# esquematico.net
KiCad netlist of a schematic drawn in Altium Designer
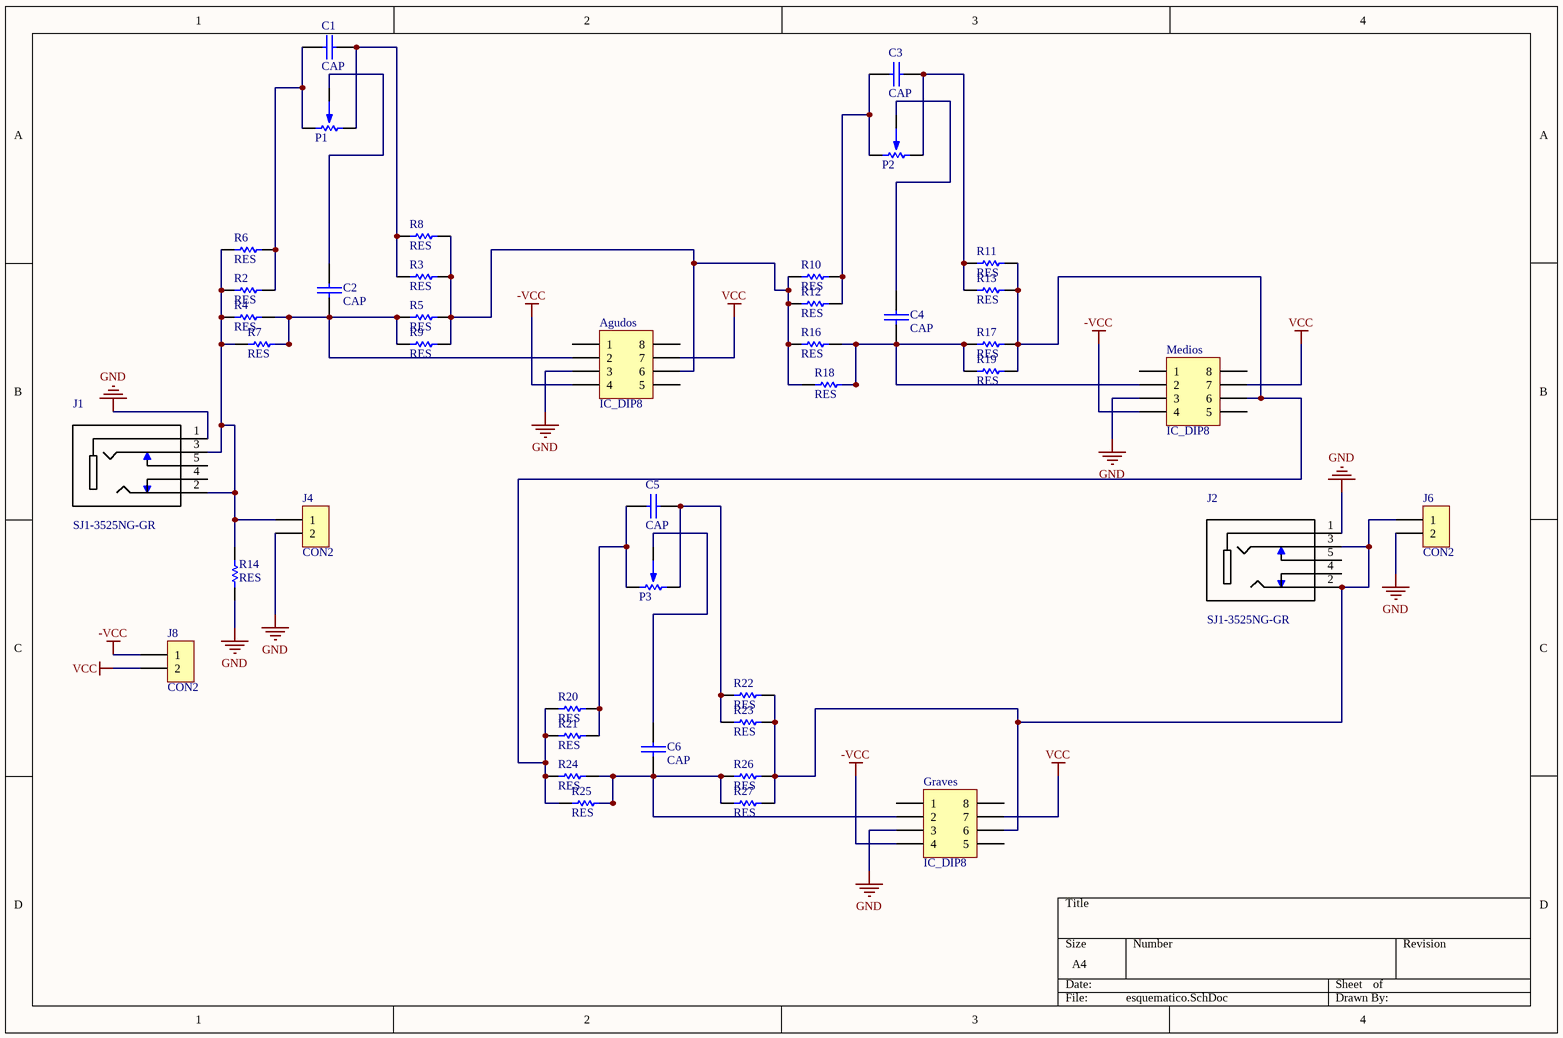
[diagram p0: esquematico.SchDoc]

(export (version "E")
  (design (tool "Eeschema 10.0.6"))
  (components
    (comp (ref "Agudos") (value "IC_DIP8") (footprint "DIP8") (libsource (lib "LIBEBAL") (part "IC_DIP8")))
    (comp (ref "C1") (value "CAP") (footprint "CAP200") (libsource (lib "LIBEBAL") (part "CAP")))
    (comp (ref "C2") (value "CAP") (footprint "CAP200") (libsource (lib "LIBEBAL") (part "CAP")))
    (comp (ref "C3") (value "CAP") (footprint "CAP200") (libsource (lib "LIBEBAL") (part "CAP")))
    (comp (ref "C4") (value "CAP") (footprint "CAP200") (libsource (lib "LIBEBAL") (part "CAP")))
    (comp (ref "C5") (value "CAP") (footprint "CAP200") (libsource (lib "LIBEBAL") (part "CAP")))
    (comp (ref "C6") (value "CAP") (footprint "CAP200") (libsource (lib "LIBEBAL") (part "CAP")))
    (comp (ref "Graves") (value "IC_DIP8") (footprint "DIP8") (libsource (lib "LIBEBAL") (part "IC_DIP8")))
    (comp (ref "J1")
      (value "SJ1-3525NG-GR")
      (footprint "CUI_SJ1-3525NG-GR")
      (libsource (lib "SJ1-3525NG-GR") (part "SJ1-3525NG-GR"))
    )
    (comp (ref "J2")
      (value "SJ1-3525NG-GR")
      (footprint "CUI_SJ1-3525NG-GR")
      (libsource (lib "SJ1-3525NG-GR") (part "SJ1-3525NG-GR"))
    )
    (comp (ref "J4") (value "CON2") (footprint "SIP2") (libsource (lib "LIBEBAL") (part "CON2")))
    (comp (ref "J6") (value "CON2") (footprint "SIP2") (libsource (lib "LIBEBAL") (part "CON2")))
    (comp (ref "J8") (value "CON2") (footprint "SIP2") (libsource (lib "LIBEBAL") (part "CON2")))
    (comp (ref "Medios") (value "IC_DIP8") (footprint "DIP8") (libsource (lib "LIBEBAL") (part "IC_DIP8")))
    (comp (ref "P1")
      (value "POTENCIOMETRO")
      (footprint "POTENCIOMETRO")
      (libsource (lib "LIBEBAL") (part "POTENCIOMETRO"))
    )
    (comp (ref "P2")
      (value "POTENCIOMETRO")
      (footprint "POTENCIOMETRO")
      (libsource (lib "LIBEBAL") (part "POTENCIOMETRO"))
    )
    (comp (ref "P3")
      (value "POTENCIOMETRO")
      (footprint "POTENCIOMETRO")
      (libsource (lib "LIBEBAL") (part "POTENCIOMETRO"))
    )
    (comp (ref "R2") (value "RES") (footprint "RES400") (libsource (lib "LIBEBAL") (part "RES")))
    (comp (ref "R3") (value "RES") (footprint "RES400") (libsource (lib "LIBEBAL") (part "RES")))
    (comp (ref "R4") (value "RES") (footprint "RES400") (libsource (lib "LIBEBAL") (part "RES")))
    (comp (ref "R5") (value "RES") (footprint "RES400") (libsource (lib "LIBEBAL") (part "RES")))
    (comp (ref "R6") (value "RES") (footprint "RES400") (libsource (lib "LIBEBAL") (part "RES")))
    (comp (ref "R7") (value "RES") (footprint "RES400") (libsource (lib "LIBEBAL") (part "RES")))
    (comp (ref "R8") (value "RES") (footprint "RES400") (libsource (lib "LIBEBAL") (part "RES")))
    (comp (ref "R9") (value "RES") (footprint "RES400") (libsource (lib "LIBEBAL") (part "RES")))
    (comp (ref "R10") (value "RES") (footprint "RES400") (libsource (lib "LIBEBAL") (part "RES")))
    (comp (ref "R11") (value "RES") (footprint "RES400") (libsource (lib "LIBEBAL") (part "RES")))
    (comp (ref "R12") (value "RES") (footprint "RES400") (libsource (lib "LIBEBAL") (part "RES")))
    (comp (ref "R13") (value "RES") (footprint "RES400") (libsource (lib "LIBEBAL") (part "RES")))
    (comp (ref "R14") (value "RES") (footprint "RES400") (libsource (lib "LIBEBAL") (part "RES")))
    (comp (ref "R16") (value "RES") (footprint "RES400") (libsource (lib "LIBEBAL") (part "RES")))
    (comp (ref "R17") (value "RES") (footprint "RES400") (libsource (lib "LIBEBAL") (part "RES")))
    (comp (ref "R18") (value "RES") (footprint "RES400") (libsource (lib "LIBEBAL") (part "RES")))
    (comp (ref "R19") (value "RES") (footprint "RES400") (libsource (lib "LIBEBAL") (part "RES")))
    (comp (ref "R20") (value "RES") (footprint "RES400") (libsource (lib "LIBEBAL") (part "RES")))
    (comp (ref "R21") (value "RES") (footprint "RES400") (libsource (lib "LIBEBAL") (part "RES")))
    (comp (ref "R22") (value "RES") (footprint "RES400") (libsource (lib "LIBEBAL") (part "RES")))
    (comp (ref "R23") (value "RES") (footprint "RES400") (libsource (lib "LIBEBAL") (part "RES")))
    (comp (ref "R24") (value "RES") (footprint "RES400") (libsource (lib "LIBEBAL") (part "RES")))
    (comp (ref "R25") (value "RES") (footprint "RES400") (libsource (lib "LIBEBAL") (part "RES")))
    (comp (ref "R26") (value "RES") (footprint "RES400") (libsource (lib "LIBEBAL") (part "RES")))
    (comp (ref "R27") (value "RES") (footprint "RES400") (libsource (lib "LIBEBAL") (part "RES")))
  )
  (nets
    (net (code "1") (name "-VCC") (class "Default")
      (node (ref "Agudos") (pin "4") (pinfunction "4_4") (pintype "passive"))
      (node (ref "Graves") (pin "4") (pinfunction "4_4") (pintype "passive"))
      (node (ref "J8") (pin "1") (pinfunction "1_1") (pintype "passive"))
      (node (ref "Medios") (pin "4") (pinfunction "4_4") (pintype "passive"))
    )
    (net (code "2") (name "GND") (class "Default")
      (node (ref "Agudos") (pin "3") (pinfunction "3_3") (pintype "passive"))
      (node (ref "Graves") (pin "3") (pinfunction "3_3") (pintype "passive"))
      (node (ref "J1") (pin "1") (pinfunction "1_1") (pintype "passive"))
      (node (ref "J2") (pin "1") (pinfunction "1_1") (pintype "passive"))
      (node (ref "J4") (pin "2") (pinfunction "2_2") (pintype "passive"))
      (node (ref "J6") (pin "2") (pinfunction "2_2") (pintype "passive"))
      (node (ref "Medios") (pin "3") (pinfunction "3_3") (pintype "passive"))
      (node (ref "R14") (pin "1") (pinfunction "1_1") (pintype "passive"))
    )
    (net (code "3") (name "Net-(Agudos-Pad2)") (class "Default")
      (node (ref "Agudos") (pin "2") (pinfunction "2_2") (pintype "passive"))
      (node (ref "C2") (pin "1") (pinfunction "1_1") (pintype "passive"))
      (node (ref "R4") (pin "2") (pinfunction "2_2") (pintype "passive"))
      (node (ref "R5") (pin "1") (pinfunction "1_1") (pintype "passive"))
      (node (ref "R7") (pin "2") (pinfunction "2_2") (pintype "passive"))
      (node (ref "R9") (pin "1") (pinfunction "1_1") (pintype "passive"))
    )
    (net (code "4") (name "Net-(Agudos-Pad6)") (class "Default")
      (node (ref "Agudos") (pin "6") (pinfunction "6_6") (pintype "passive"))
      (node (ref "R10") (pin "1") (pinfunction "1_1") (pintype "passive"))
      (node (ref "R12") (pin "1") (pinfunction "1_1") (pintype "passive"))
      (node (ref "R16") (pin "1") (pinfunction "1_1") (pintype "passive"))
      (node (ref "R18") (pin "1") (pinfunction "1_1") (pintype "passive"))
      (node (ref "R3") (pin "2") (pinfunction "2_2") (pintype "passive"))
      (node (ref "R5") (pin "2") (pinfunction "2_2") (pintype "passive"))
      (node (ref "R8") (pin "2") (pinfunction "2_2") (pintype "passive"))
      (node (ref "R9") (pin "2") (pinfunction "2_2") (pintype "passive"))
    )
    (net (code "5") (name "Net-(C1-Pad1)") (class "Default")
      (node (ref "C1") (pin "1") (pinfunction "1_1") (pintype "passive"))
      (node (ref "P1") (pin "1") (pinfunction "1_1") (pintype "passive"))
      (node (ref "R2") (pin "2") (pinfunction "2_2") (pintype "passive"))
      (node (ref "R6") (pin "2") (pinfunction "2_2") (pintype "passive"))
    )
    (net (code "6") (name "Net-(C1-Pad2)") (class "Default")
      (node (ref "C1") (pin "2") (pinfunction "2_2") (pintype "passive"))
      (node (ref "P1") (pin "3") (pinfunction "3_3") (pintype "passive"))
      (node (ref "R3") (pin "1") (pinfunction "1_1") (pintype "passive"))
      (node (ref "R8") (pin "1") (pinfunction "1_1") (pintype "passive"))
    )
    (net (code "7") (name "Net-(C2-Pad2)") (class "Default")
      (node (ref "C2") (pin "2") (pinfunction "2_2") (pintype "passive"))
      (node (ref "P1") (pin "2") (pinfunction "2_2") (pintype "passive"))
    )
    (net (code "8") (name "Net-(C3-Pad1)") (class "Default")
      (node (ref "C3") (pin "1") (pinfunction "1_1") (pintype "passive"))
      (node (ref "P2") (pin "1") (pinfunction "1_1") (pintype "passive"))
      (node (ref "R10") (pin "2") (pinfunction "2_2") (pintype "passive"))
      (node (ref "R12") (pin "2") (pinfunction "2_2") (pintype "passive"))
    )
    (net (code "9") (name "Net-(C3-Pad2)") (class "Default")
      (node (ref "C3") (pin "2") (pinfunction "2_2") (pintype "passive"))
      (node (ref "P2") (pin "3") (pinfunction "3_3") (pintype "passive"))
      (node (ref "R11") (pin "1") (pinfunction "1_1") (pintype "passive"))
      (node (ref "R13") (pin "1") (pinfunction "1_1") (pintype "passive"))
    )
    (net (code "10") (name "Net-(C4-Pad1)") (class "Default")
      (node (ref "C4") (pin "1") (pinfunction "1_1") (pintype "passive"))
      (node (ref "Medios") (pin "2") (pinfunction "2_2") (pintype "passive"))
      (node (ref "R16") (pin "2") (pinfunction "2_2") (pintype "passive"))
      (node (ref "R17") (pin "1") (pinfunction "1_1") (pintype "passive"))
      (node (ref "R18") (pin "2") (pinfunction "2_2") (pintype "passive"))
      (node (ref "R19") (pin "1") (pinfunction "1_1") (pintype "passive"))
    )
    (net (code "11") (name "Net-(C4-Pad2)") (class "Default")
      (node (ref "C4") (pin "2") (pinfunction "2_2") (pintype "passive"))
      (node (ref "P2") (pin "2") (pinfunction "2_2") (pintype "passive"))
    )
    (net (code "12") (name "Net-(C5-Pad1)") (class "Default")
      (node (ref "C5") (pin "1") (pinfunction "1_1") (pintype "passive"))
      (node (ref "P3") (pin "1") (pinfunction "1_1") (pintype "passive"))
      (node (ref "R20") (pin "2") (pinfunction "2_2") (pintype "passive"))
      (node (ref "R21") (pin "2") (pinfunction "2_2") (pintype "passive"))
    )
    (net (code "13") (name "Net-(C5-Pad2)") (class "Default")
      (node (ref "C5") (pin "2") (pinfunction "2_2") (pintype "passive"))
      (node (ref "P3") (pin "3") (pinfunction "3_3") (pintype "passive"))
      (node (ref "R22") (pin "1") (pinfunction "1_1") (pintype "passive"))
      (node (ref "R23") (pin "1") (pinfunction "1_1") (pintype "passive"))
    )
    (net (code "14") (name "Net-(C6-Pad1)") (class "Default")
      (node (ref "C6") (pin "1") (pinfunction "1_1") (pintype "passive"))
      (node (ref "Graves") (pin "2") (pinfunction "2_2") (pintype "passive"))
      (node (ref "R24") (pin "2") (pinfunction "2_2") (pintype "passive"))
      (node (ref "R25") (pin "2") (pinfunction "2_2") (pintype "passive"))
      (node (ref "R26") (pin "1") (pinfunction "1_1") (pintype "passive"))
      (node (ref "R27") (pin "1") (pinfunction "1_1") (pintype "passive"))
    )
    (net (code "15") (name "Net-(C6-Pad2)") (class "Default")
      (node (ref "C6") (pin "2") (pinfunction "2_2") (pintype "passive"))
      (node (ref "P3") (pin "2") (pinfunction "2_2") (pintype "passive"))
    )
    (net (code "16") (name "Net-(Graves-Pad6)") (class "Default")
      (node (ref "Graves") (pin "6") (pinfunction "6_6") (pintype "passive"))
      (node (ref "J2") (pin "2") (pinfunction "2_2") (pintype "passive"))
      (node (ref "J2") (pin "3") (pinfunction "3_3") (pintype "passive"))
      (node (ref "J6") (pin "1") (pinfunction "1_1") (pintype "passive"))
      (node (ref "R22") (pin "2") (pinfunction "2_2") (pintype "passive"))
      (node (ref "R23") (pin "2") (pinfunction "2_2") (pintype "passive"))
      (node (ref "R26") (pin "2") (pinfunction "2_2") (pintype "passive"))
      (node (ref "R27") (pin "2") (pinfunction "2_2") (pintype "passive"))
    )
    (net (code "17") (name "Net-(J1-Pad2)") (class "Default")
      (node (ref "J1") (pin "2") (pinfunction "2_2") (pintype "passive"))
      (node (ref "J1") (pin "3") (pinfunction "3_3") (pintype "passive"))
      (node (ref "J4") (pin "1") (pinfunction "1_1") (pintype "passive"))
      (node (ref "R14") (pin "2") (pinfunction "2_2") (pintype "passive"))
      (node (ref "R2") (pin "1") (pinfunction "1_1") (pintype "passive"))
      (node (ref "R4") (pin "1") (pinfunction "1_1") (pintype "passive"))
      (node (ref "R6") (pin "1") (pinfunction "1_1") (pintype "passive"))
      (node (ref "R7") (pin "1") (pinfunction "1_1") (pintype "passive"))
    )
    (net (code "18") (name "Net-(Medios-Pad6)") (class "Default")
      (node (ref "Medios") (pin "6") (pinfunction "6_6") (pintype "passive"))
      (node (ref "R11") (pin "2") (pinfunction "2_2") (pintype "passive"))
      (node (ref "R13") (pin "2") (pinfunction "2_2") (pintype "passive"))
      (node (ref "R17") (pin "2") (pinfunction "2_2") (pintype "passive"))
      (node (ref "R19") (pin "2") (pinfunction "2_2") (pintype "passive"))
      (node (ref "R20") (pin "1") (pinfunction "1_1") (pintype "passive"))
      (node (ref "R21") (pin "1") (pinfunction "1_1") (pintype "passive"))
      (node (ref "R24") (pin "1") (pinfunction "1_1") (pintype "passive"))
      (node (ref "R25") (pin "1") (pinfunction "1_1") (pintype "passive"))
    )
    (net (code "19") (name "VCC") (class "Default")
      (node (ref "Agudos") (pin "7") (pinfunction "7_7") (pintype "passive"))
      (node (ref "Graves") (pin "7") (pinfunction "7_7") (pintype "passive"))
      (node (ref "J8") (pin "2") (pinfunction "2_2") (pintype "passive"))
      (node (ref "Medios") (pin "7") (pinfunction "7_7") (pintype "passive"))
    )
    (net (code "20") (name "unconnected-(Agudos-Pad1)") (class "Default")
      (node (ref "Agudos") (pin "1") (pinfunction "1_1") (pintype "passive"))
    )
    (net (code "21") (name "unconnected-(Agudos-Pad5)") (class "Default")
      (node (ref "Agudos") (pin "5") (pinfunction "5_5") (pintype "passive"))
    )
    (net (code "22") (name "unconnected-(Agudos-Pad8)") (class "Default")
      (node (ref "Agudos") (pin "8") (pinfunction "8_8") (pintype "passive"))
    )
    (net (code "23") (name "unconnected-(Graves-Pad1)") (class "Default")
      (node (ref "Graves") (pin "1") (pinfunction "1_1") (pintype "passive"))
    )
    (net (code "24") (name "unconnected-(Graves-Pad5)") (class "Default")
      (node (ref "Graves") (pin "5") (pinfunction "5_5") (pintype "passive"))
    )
    (net (code "25") (name "unconnected-(Graves-Pad8)") (class "Default")
      (node (ref "Graves") (pin "8") (pinfunction "8_8") (pintype "passive"))
    )
    (net (code "26") (name "unconnected-(J1-Pad4)") (class "Default")
      (node (ref "J1") (pin "4") (pinfunction "4_4") (pintype "passive"))
    )
    (net (code "27") (name "unconnected-(J1-Pad5)") (class "Default")
      (node (ref "J1") (pin "5") (pinfunction "5_5") (pintype "passive"))
    )
    (net (code "28") (name "unconnected-(J2-Pad4)") (class "Default")
      (node (ref "J2") (pin "4") (pinfunction "4_4") (pintype "passive"))
    )
    (net (code "29") (name "unconnected-(J2-Pad5)") (class "Default")
      (node (ref "J2") (pin "5") (pinfunction "5_5") (pintype "passive"))
    )
    (net (code "30") (name "unconnected-(Medios-Pad1)") (class "Default")
      (node (ref "Medios") (pin "1") (pinfunction "1_1") (pintype "passive"))
    )
    (net (code "31") (name "unconnected-(Medios-Pad5)") (class "Default")
      (node (ref "Medios") (pin "5") (pinfunction "5_5") (pintype "passive"))
    )
    (net (code "32") (name "unconnected-(Medios-Pad8)") (class "Default")
      (node (ref "Medios") (pin "8") (pinfunction "8_8") (pintype "passive"))
    )
  )
)
